# Serial.net
KiCad netlist of a schematic drawn in Altium Designer
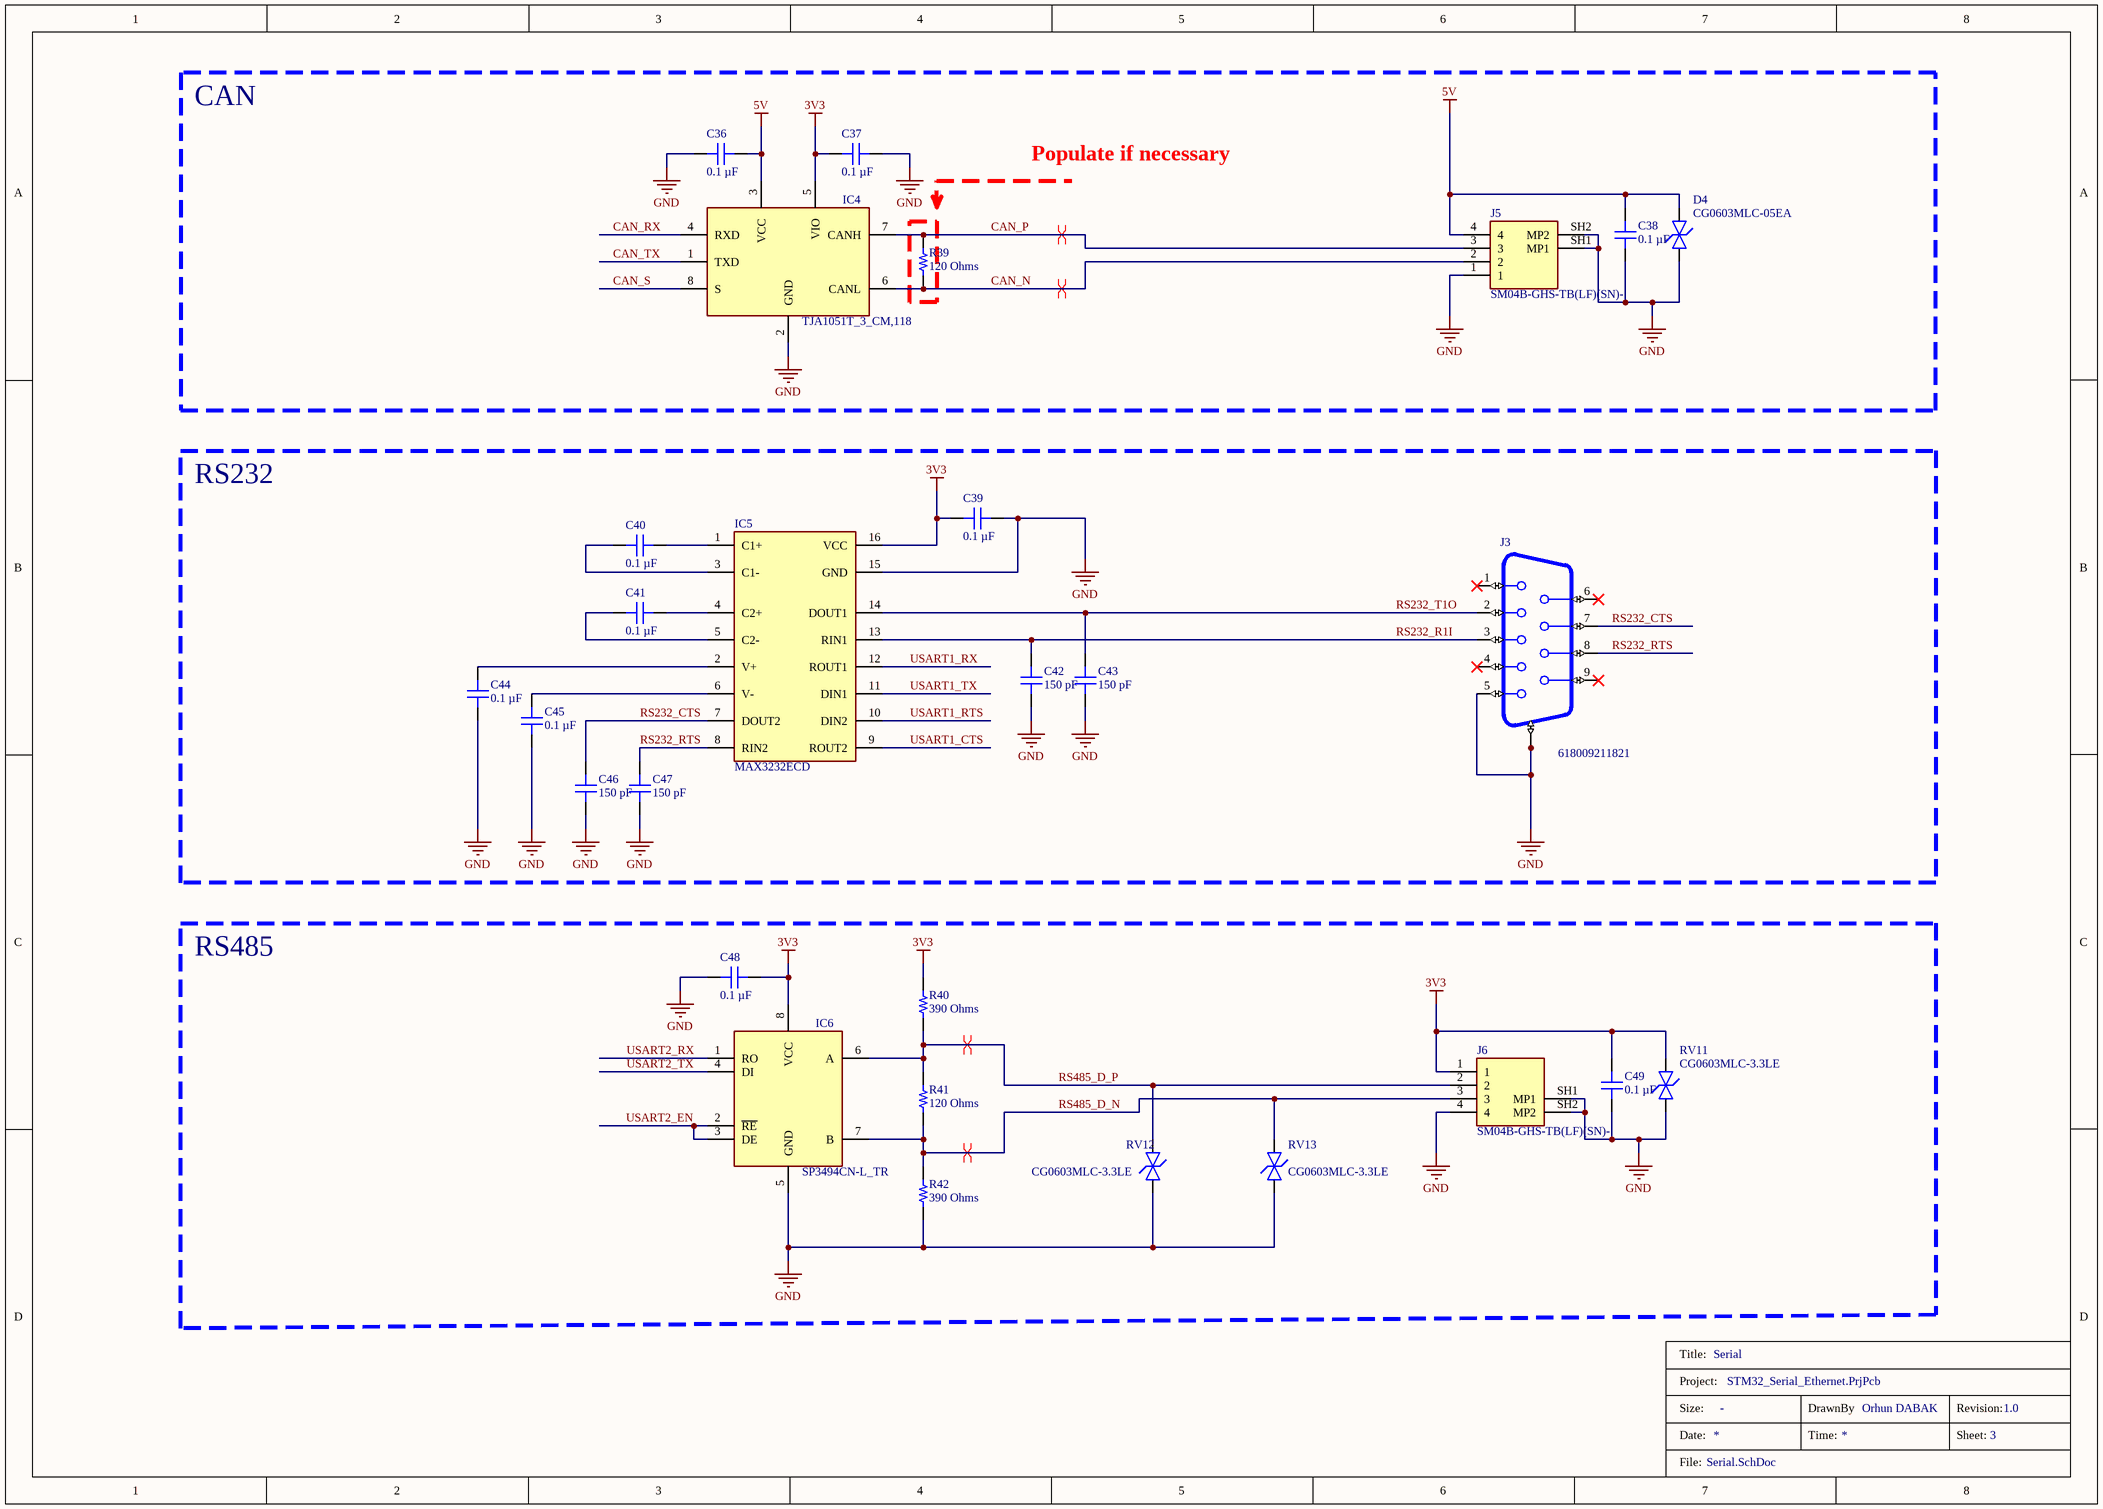
[diagram p0: Serial.SchDoc]

(export (version "E")
  (design (tool "Eeschema 10.0.6"))
  (components
    (comp (ref "C36")
      (value "0.1 µF")
      (footprint "CAP 0603_1608")
      (description "CAP CER 0.1UF 16V X7R 0603")
      (fields (field (name "PART NUMBER") "CS0603KRX7R7BB104") (field (name "MANUFACTURER") "Yageo"))
      (libsource (lib "Celestial Altium Library - altium_library") (part "Capacitor"))
    )
    (comp (ref "C37")
      (value "0.1 µF")
      (footprint "CAP 0603_1608")
      (description "CAP CER 0.1UF 16V X7R 0603")
      (fields (field (name "PART NUMBER") "CS0603KRX7R7BB104") (field (name "MANUFACTURER") "Yageo"))
      (libsource (lib "Celestial Altium Library - altium_library") (part "Capacitor"))
    )
    (comp (ref "C38")
      (value "0.1 µF")
      (footprint "CAP 0603_1608")
      (description "CAP CER 0.1UF 16V X7R 0603")
      (fields (field (name "PART NUMBER") "CS0603KRX7R7BB104") (field (name "MANUFACTURER") "Yageo"))
      (libsource (lib "Celestial Altium Library - altium_library") (part "Capacitor"))
    )
    (comp (ref "C39")
      (value "0.1 µF")
      (footprint "CAP 0603_1608")
      (description "CAP CER 0.1UF 16V X7R 0603")
      (fields (field (name "PART NUMBER") "CS0603KRX7R7BB104") (field (name "MANUFACTURER") "Yageo"))
      (libsource (lib "Celestial Altium Library - altium_library") (part "Capacitor"))
    )
    (comp (ref "C40")
      (value "0.1 µF")
      (footprint "CAP 0603_1608")
      (description "CAP CER 0.1UF 16V X7R 0603")
      (fields (field (name "PART NUMBER") "CS0603KRX7R7BB104") (field (name "MANUFACTURER") "Yageo"))
      (libsource (lib "Celestial Altium Library - altium_library") (part "Capacitor"))
    )
    (comp (ref "C41")
      (value "0.1 µF")
      (footprint "CAP 0603_1608")
      (description "CAP CER 0.1UF 16V X7R 0603")
      (fields (field (name "PART NUMBER") "CS0603KRX7R7BB104") (field (name "MANUFACTURER") "Yageo"))
      (libsource (lib "Celestial Altium Library - altium_library") (part "Capacitor"))
    )
    (comp (ref "C42")
      (value "150 pF")
      (footprint "CAP 0603_1608")
      (description "CAP CER 150PF 16V X7R 0603")
      (fields (field (name "PART NUMBER") "885012206029") (field (name "MANUFACTURER") "Würth Elektronik"))
      (libsource (lib "Celestial Altium Library - altium_library") (part "Capacitor"))
    )
    (comp (ref "C43")
      (value "150 pF")
      (footprint "CAP 0603_1608")
      (description "CAP CER 150PF 16V X7R 0603")
      (fields (field (name "PART NUMBER") "885012206029") (field (name "MANUFACTURER") "Würth Elektronik"))
      (libsource (lib "Celestial Altium Library - altium_library") (part "Capacitor"))
    )
    (comp (ref "C44")
      (value "0.1 µF")
      (footprint "CAP 0603_1608")
      (description "CAP CER 0.1UF 16V X7R 0603")
      (fields (field (name "PART NUMBER") "CS0603KRX7R7BB104") (field (name "MANUFACTURER") "Yageo"))
      (libsource (lib "Celestial Altium Library - altium_library") (part "Capacitor"))
    )
    (comp (ref "C45")
      (value "0.1 µF")
      (footprint "CAP 0603_1608")
      (description "CAP CER 0.1UF 16V X7R 0603")
      (fields (field (name "PART NUMBER") "CS0603KRX7R7BB104") (field (name "MANUFACTURER") "Yageo"))
      (libsource (lib "Celestial Altium Library - altium_library") (part "Capacitor"))
    )
    (comp (ref "C46")
      (value "150 pF")
      (footprint "CAP 0603_1608")
      (description "CAP CER 150PF 16V X7R 0603")
      (fields (field (name "PART NUMBER") "885012206029") (field (name "MANUFACTURER") "Würth Elektronik"))
      (libsource (lib "Celestial Altium Library - altium_library") (part "Capacitor"))
    )
    (comp (ref "C47")
      (value "150 pF")
      (footprint "CAP 0603_1608")
      (description "CAP CER 150PF 16V X7R 0603")
      (fields (field (name "PART NUMBER") "885012206029") (field (name "MANUFACTURER") "Würth Elektronik"))
      (libsource (lib "Celestial Altium Library - altium_library") (part "Capacitor"))
    )
    (comp (ref "C48")
      (value "0.1 µF")
      (footprint "CAP 0603_1608")
      (description "CAP CER 0.1UF 16V X7R 0603")
      (fields (field (name "PART NUMBER") "CS0603KRX7R7BB104") (field (name "MANUFACTURER") "Yageo"))
      (libsource (lib "Celestial Altium Library - altium_library") (part "Capacitor"))
    )
    (comp (ref "C49")
      (value "0.1 µF")
      (footprint "CAP 0603_1608")
      (description "CAP CER 0.1UF 16V X7R 0603")
      (fields (field (name "PART NUMBER") "CS0603KRX7R7BB104") (field (name "MANUFACTURER") "Yageo"))
      (libsource (lib "Celestial Altium Library - altium_library") (part "Capacitor"))
    )
    (comp (ref "D4")
      (value "CG0603MLC-05EA")
      (footprint "SamacSys:DIONC1608X55N")
      (description "TVS Diode (Bi-directional)")
      (libsource (lib "SamacSys") (part "CG0603MLC-05EA"))
    )
    (comp (ref "IC4")
      (value "TJA1051T_3_CM,118")
      (footprint "SamacSys:SOIC127P600X175-8N")
      (description "Integrated Circuit")
      (fields
        (field (name "MANUFACTURER_PART_NUMBER") "TJA1051T/3/CM,118")
        (field (name "MOUSER PART NUMBER") "771-TJA1051T/3CM118")
      )
      (libsource (lib "SamacSys") (part "TJA1051T_3_CM,118"))
    )
    (comp (ref "IC5")
      (value "MAX3232ECD")
      (footprint "SamacSys:SOIC127P600X175-16N")
      (description "Integrated Circuit")
      (fields (field (name "MOUSER PART NUMBER") "595-MAX3232ECD"))
      (libsource (lib "SamacSys") (part "MAX3232ECD"))
    )
    (comp (ref "IC6")
      (value "SP3494CN-L_TR")
      (footprint "SamacSys:SOIC127P600X175-8N")
      (description "Integrated Circuit")
      (fields
        (field (name "MANUFACTURER_PART_NUMBER") "SP3494CN-L/TR")
        (field (name "MOUSER PART NUMBER") "701-SP3494CN-L/TR")
      )
      (libsource (lib "SamacSys") (part "SP3494CN-L_TR"))
    )
    (comp (ref "J3")
      (value "618009211821")
      (footprint "618009211821")
      (description "9 Position D-Sub Receptacle, Female Sockets Connector")
      (fields (field (name "MF") "WÃ¼rth Elektronik"))
      (libsource (lib "618009211821") (part "618009211821"))
    )
    (comp (ref "J5")
      (value "SM04B-GHS-TB(LF)(SN)-")
      (footprint "SnapEDApcb:JST_SM04B-GHS-TB(LF)(SN)-")
      (description "Connector Header Surface Mount, Right Angle 4 position 0.049 _1.25mm_")
      (fields (field (name "MP") "SM04B-GHS-TB_LF__SN_-") (field (name "MF") "JST Sales"))
      (libsource (lib "SnapEDAsch") (part "SM04B-GHS-TB(LF)(SN)-"))
    )
    (comp (ref "J6")
      (value "SM04B-GHS-TB(LF)(SN)-")
      (footprint "SnapEDApcb:JST_SM04B-GHS-TB(LF)(SN)-")
      (description "Connector Header Surface Mount, Right Angle 4 position 0.049 _1.25mm_")
      (fields (field (name "MP") "SM04B-GHS-TB_LF__SN_-") (field (name "MF") "JST Sales"))
      (libsource (lib "") (part "SM04B-GHS-TB(LF)(SN)-_1"))
    )
    (comp (ref "R39")
      (value "120 Ohms")
      (footprint "RES 0603_1608")
      (description "RES SMD 120 OHM 5% 1/10W 0603")
      (fields (field (name "PART NUMBER") "CRCW0603120RJNEA") (field (name "MANUFACTURER") "Vishay Dale"))
      (libsource (lib "Celestial Altium Library - altium_library") (part "Resistor"))
    )
    (comp (ref "R40")
      (value "390 Ohms")
      (footprint "RES 0603_1608")
      (description "RES 390 OHM 1% 1/4W 0603")
      (fields
        (field (name "PART NUMBER") "CRGP0603F390R")
        (field (name "MANUFACTURER") "TE Connectivity Passive Product")
      )
      (libsource (lib "Celestial Altium Library - altium_library") (part "Resistor"))
    )
    (comp (ref "R41")
      (value "120 Ohms")
      (footprint "RES 0603_1608")
      (description "RES SMD 120 OHM 5% 1/10W 0603")
      (fields (field (name "PART NUMBER") "CRCW0603120RJNEA") (field (name "MANUFACTURER") "Vishay Dale"))
      (libsource (lib "Celestial Altium Library - altium_library") (part "Resistor"))
    )
    (comp (ref "R42")
      (value "390 Ohms")
      (footprint "RES 0603_1608")
      (description "RES 390 OHM 1% 1/4W 0603")
      (fields
        (field (name "PART NUMBER") "CRGP0603F390R")
        (field (name "MANUFACTURER") "TE Connectivity Passive Product")
      )
      (libsource (lib "Celestial Altium Library - altium_library") (part "Resistor"))
    )
    (comp (ref "RV11")
      (value "CG0603MLC-3.3LE")
      (footprint "SamacSys:VARC1608X55N")
      (description "Varistor")
      (fields (field (name "MOUSER PART NUMBER") "652-CG0603MLC-3.3LE"))
      (libsource (lib "SamacSys") (part "CG0603MLC-3.3LE"))
    )
    (comp (ref "RV12")
      (value "CG0603MLC-3.3LE")
      (footprint "SamacSys:VARC1608X55N")
      (description "Varistor")
      (fields (field (name "MOUSER PART NUMBER") "652-CG0603MLC-3.3LE"))
      (libsource (lib "SamacSys") (part "CG0603MLC-3.3LE"))
    )
    (comp (ref "RV13")
      (value "CG0603MLC-3.3LE")
      (footprint "SamacSys:VARC1608X55N")
      (description "Varistor")
      (fields (field (name "MOUSER PART NUMBER") "652-CG0603MLC-3.3LE"))
      (libsource (lib "SamacSys") (part "CG0603MLC-3.3LE"))
    )
  )
  (nets
    (net (code "1") (name "/CAN_N") (class "Default")
      (node (ref "IC4") (pin "6") (pinfunction "CANL_6") (pintype "passive"))
      (node (ref "J5") (pin "2") (pinfunction "2_2") (pintype "passive"))
      (node (ref "R39") (pin "1") (pinfunction "1_1") (pintype "passive"))
    )
    (net (code "2") (name "/CAN_P") (class "Default")
      (node (ref "IC4") (pin "7") (pinfunction "CANH_7") (pintype "passive"))
      (node (ref "J5") (pin "3") (pinfunction "3_3") (pintype "passive"))
      (node (ref "R39") (pin "2") (pinfunction "2_2") (pintype "passive"))
    )
    (net (code "3") (name "/CAN_RX") (class "Default")
      (node (ref "IC4") (pin "4") (pinfunction "RXD_4") (pintype "passive"))
    )
    (net (code "4") (name "/CAN_S") (class "Default")
      (node (ref "IC4") (pin "8") (pinfunction "S_8") (pintype "passive"))
    )
    (net (code "5") (name "/CAN_TX") (class "Default")
      (node (ref "IC4") (pin "1") (pinfunction "TXD_1") (pintype "passive"))
    )
    (net (code "6") (name "/RS232_CTS") (class "Default")
      (node (ref "C46") (pin "2") (pinfunction "2_2") (pintype "passive"))
      (node (ref "IC5") (pin "7") (pinfunction "DOUT2_7") (pintype "passive"))
      (node (ref "J3") (pin "7") (pinfunction "7_7") (pintype "bidirectional"))
    )
    (net (code "7") (name "/RS232_R1I") (class "Default")
      (node (ref "C42") (pin "2") (pinfunction "2_2") (pintype "passive"))
      (node (ref "IC5") (pin "13") (pinfunction "RIN1_13") (pintype "passive"))
      (node (ref "J3") (pin "3") (pinfunction "3_3") (pintype "bidirectional"))
    )
    (net (code "8") (name "/RS232_RTS") (class "Default")
      (node (ref "C47") (pin "2") (pinfunction "2_2") (pintype "passive"))
      (node (ref "IC5") (pin "8") (pinfunction "RIN2_8") (pintype "passive"))
      (node (ref "J3") (pin "8") (pinfunction "8_8") (pintype "bidirectional"))
    )
    (net (code "9") (name "/RS232_T1O") (class "Default")
      (node (ref "C43") (pin "2") (pinfunction "2_2") (pintype "passive"))
      (node (ref "IC5") (pin "14") (pinfunction "DOUT1_14") (pintype "passive"))
      (node (ref "J3") (pin "2") (pinfunction "2_2") (pintype "bidirectional"))
    )
    (net (code "10") (name "/RS485_D_N") (class "Default")
      (node (ref "IC6") (pin "7") (pinfunction "B_7") (pintype "passive"))
      (node (ref "J6") (pin "3") (pinfunction "3_3") (pintype "passive"))
      (node (ref "R41") (pin "1") (pinfunction "1_1") (pintype "passive"))
      (node (ref "R42") (pin "2") (pinfunction "2_2") (pintype "passive"))
      (node (ref "RV13") (pin "2") (pinfunction "2_2") (pintype "passive"))
    )
    (net (code "11") (name "/RS485_D_P") (class "Default")
      (node (ref "IC6") (pin "6") (pinfunction "A_6") (pintype "passive"))
      (node (ref "J6") (pin "2") (pinfunction "2_2") (pintype "passive"))
      (node (ref "R40") (pin "1") (pinfunction "1_1") (pintype "passive"))
      (node (ref "R41") (pin "2") (pinfunction "2_2") (pintype "passive"))
      (node (ref "RV12") (pin "2") (pinfunction "2_2") (pintype "passive"))
    )
    (net (code "12") (name "/USART1_CTS") (class "Default")
      (node (ref "IC5") (pin "9") (pinfunction "ROUT2_9") (pintype "passive"))
    )
    (net (code "13") (name "/USART1_RTS") (class "Default")
      (node (ref "IC5") (pin "10") (pinfunction "DIN2_10") (pintype "passive"))
    )
    (net (code "14") (name "/USART1_RX") (class "Default")
      (node (ref "IC5") (pin "12") (pinfunction "ROUT1_12") (pintype "passive"))
    )
    (net (code "15") (name "/USART1_TX") (class "Default")
      (node (ref "IC5") (pin "11") (pinfunction "DIN1_11") (pintype "passive"))
    )
    (net (code "16") (name "/USART2_EN") (class "Default")
      (node (ref "IC6") (pin "2") (pinfunction "~{RE}_2") (pintype "passive"))
      (node (ref "IC6") (pin "3") (pinfunction "DE_3") (pintype "passive"))
    )
    (net (code "17") (name "/USART2_RX") (class "Default")
      (node (ref "IC6") (pin "1") (pinfunction "RO_1") (pintype "passive"))
    )
    (net (code "18") (name "/USART2_TX") (class "Default")
      (node (ref "IC6") (pin "4") (pinfunction "DI_4") (pintype "passive"))
    )
    (net (code "19") (name "3V3") (class "Default")
      (node (ref "C37") (pin "2") (pinfunction "2_2") (pintype "passive"))
      (node (ref "C39") (pin "2") (pinfunction "2_2") (pintype "passive"))
      (node (ref "C48") (pin "1") (pinfunction "1_1") (pintype "passive"))
      (node (ref "C49") (pin "2") (pinfunction "2_2") (pintype "passive"))
      (node (ref "IC4") (pin "5") (pinfunction "VIO_5") (pintype "passive"))
      (node (ref "IC5") (pin "16") (pinfunction "VCC_16") (pintype "passive"))
      (node (ref "IC6") (pin "8") (pinfunction "VCC_8") (pintype "passive"))
      (node (ref "J6") (pin "1") (pinfunction "1_1") (pintype "passive"))
      (node (ref "R40") (pin "2") (pinfunction "2_2") (pintype "passive"))
      (node (ref "RV11") (pin "2") (pinfunction "2_2") (pintype "passive"))
    )
    (net (code "20") (name "5V") (class "Default")
      (node (ref "C36") (pin "1") (pinfunction "1_1") (pintype "passive"))
      (node (ref "C38") (pin "2") (pinfunction "2_2") (pintype "passive"))
      (node (ref "D4") (pin "2") (pinfunction "2_2") (pintype "passive"))
      (node (ref "IC4") (pin "3") (pinfunction "VCC_3") (pintype "power_in"))
      (node (ref "J5") (pin "4") (pinfunction "4_4") (pintype "passive"))
    )
    (net (code "21") (name "GND") (class "Default")
      (node (ref "C36") (pin "2") (pinfunction "2_2") (pintype "passive"))
      (node (ref "C37") (pin "1") (pinfunction "1_1") (pintype "passive"))
      (node (ref "C38") (pin "1") (pinfunction "1_1") (pintype "passive"))
      (node (ref "C39") (pin "1") (pinfunction "1_1") (pintype "passive"))
      (node (ref "C42") (pin "1") (pinfunction "1_1") (pintype "passive"))
      (node (ref "C43") (pin "1") (pinfunction "1_1") (pintype "passive"))
      (node (ref "C44") (pin "1") (pinfunction "1_1") (pintype "passive"))
      (node (ref "C45") (pin "1") (pinfunction "1_1") (pintype "passive"))
      (node (ref "C46") (pin "1") (pinfunction "1_1") (pintype "passive"))
      (node (ref "C47") (pin "1") (pinfunction "1_1") (pintype "passive"))
      (node (ref "C48") (pin "2") (pinfunction "2_2") (pintype "passive"))
      (node (ref "C49") (pin "1") (pinfunction "1_1") (pintype "passive"))
      (node (ref "D4") (pin "1") (pinfunction "1_1") (pintype "passive"))
      (node (ref "IC4") (pin "2") (pinfunction "GND_2") (pintype "power_in"))
      (node (ref "IC5") (pin "15") (pinfunction "GND_15") (pintype "passive"))
      (node (ref "IC6") (pin "5") (pinfunction "GND_5") (pintype "passive"))
      (node (ref "J3") (pin "5") (pinfunction "5_5") (pintype "bidirectional"))
      (node (ref "J3") (pin "Z1") (pinfunction "SHIELD_Z1") (pintype "bidirectional"))
      (node (ref "J3") (pin "Z2") (pinfunction "SHIELD_Z2") (pintype "bidirectional"))
      (node (ref "J5") (pin "1") (pinfunction "1_1") (pintype "passive"))
      (node (ref "J5") (pin "SH1") (pinfunction "MP1_SH1") (pintype "passive"))
      (node (ref "J5") (pin "SH2") (pinfunction "MP2_SH2") (pintype "passive"))
      (node (ref "J6") (pin "4") (pinfunction "4_4") (pintype "passive"))
      (node (ref "J6") (pin "SH1") (pinfunction "MP1_SH1") (pintype "passive"))
      (node (ref "J6") (pin "SH2") (pinfunction "MP2_SH2") (pintype "passive"))
      (node (ref "R42") (pin "1") (pinfunction "1_1") (pintype "passive"))
      (node (ref "RV11") (pin "1") (pinfunction "1_1") (pintype "passive"))
      (node (ref "RV12") (pin "1") (pinfunction "1_1") (pintype "passive"))
      (node (ref "RV13") (pin "1") (pinfunction "1_1") (pintype "passive"))
    )
    (net (code "22") (name "Net-(IC5-C1+)") (class "Default")
      (node (ref "C40") (pin "1") (pinfunction "1_1") (pintype "passive"))
      (node (ref "IC5") (pin "1") (pinfunction "C1+_1") (pintype "passive"))
    )
    (net (code "23") (name "Net-(IC5-C1-)") (class "Default")
      (node (ref "C40") (pin "2") (pinfunction "2_2") (pintype "passive"))
      (node (ref "IC5") (pin "3") (pinfunction "C1-_3") (pintype "passive"))
    )
    (net (code "24") (name "Net-(IC5-C2+)") (class "Default")
      (node (ref "C41") (pin "1") (pinfunction "1_1") (pintype "passive"))
      (node (ref "IC5") (pin "4") (pinfunction "C2+_4") (pintype "passive"))
    )
    (net (code "25") (name "Net-(IC5-C2-)") (class "Default")
      (node (ref "C41") (pin "2") (pinfunction "2_2") (pintype "passive"))
      (node (ref "IC5") (pin "5") (pinfunction "C2-_5") (pintype "passive"))
    )
    (net (code "26") (name "Net-(IC5-V+)") (class "Default")
      (node (ref "C44") (pin "2") (pinfunction "2_2") (pintype "passive"))
      (node (ref "IC5") (pin "2") (pinfunction "V+_2") (pintype "passive"))
    )
    (net (code "27") (name "Net-(IC5-V-)") (class "Default")
      (node (ref "C45") (pin "2") (pinfunction "2_2") (pintype "passive"))
      (node (ref "IC5") (pin "6") (pinfunction "V-_6") (pintype "passive"))
    )
    (net (code "28") (name "unconnected-(J3-Pad1)") (class "Default")
      (node (ref "J3") (pin "1") (pinfunction "1_1") (pintype "bidirectional+no_connect"))
    )
    (net (code "29") (name "unconnected-(J3-Pad4)") (class "Default")
      (node (ref "J3") (pin "4") (pinfunction "4_4") (pintype "bidirectional+no_connect"))
    )
    (net (code "30") (name "unconnected-(J3-Pad6)") (class "Default")
      (node (ref "J3") (pin "6") (pinfunction "6_6") (pintype "bidirectional+no_connect"))
    )
    (net (code "31") (name "unconnected-(J3-Pad9)") (class "Default")
      (node (ref "J3") (pin "9") (pinfunction "9_9") (pintype "bidirectional+no_connect"))
    )
  )
)
